# module_S-RX28_rev3_3_644.net
KiCad netlist of a schematic drawn in EAGLE
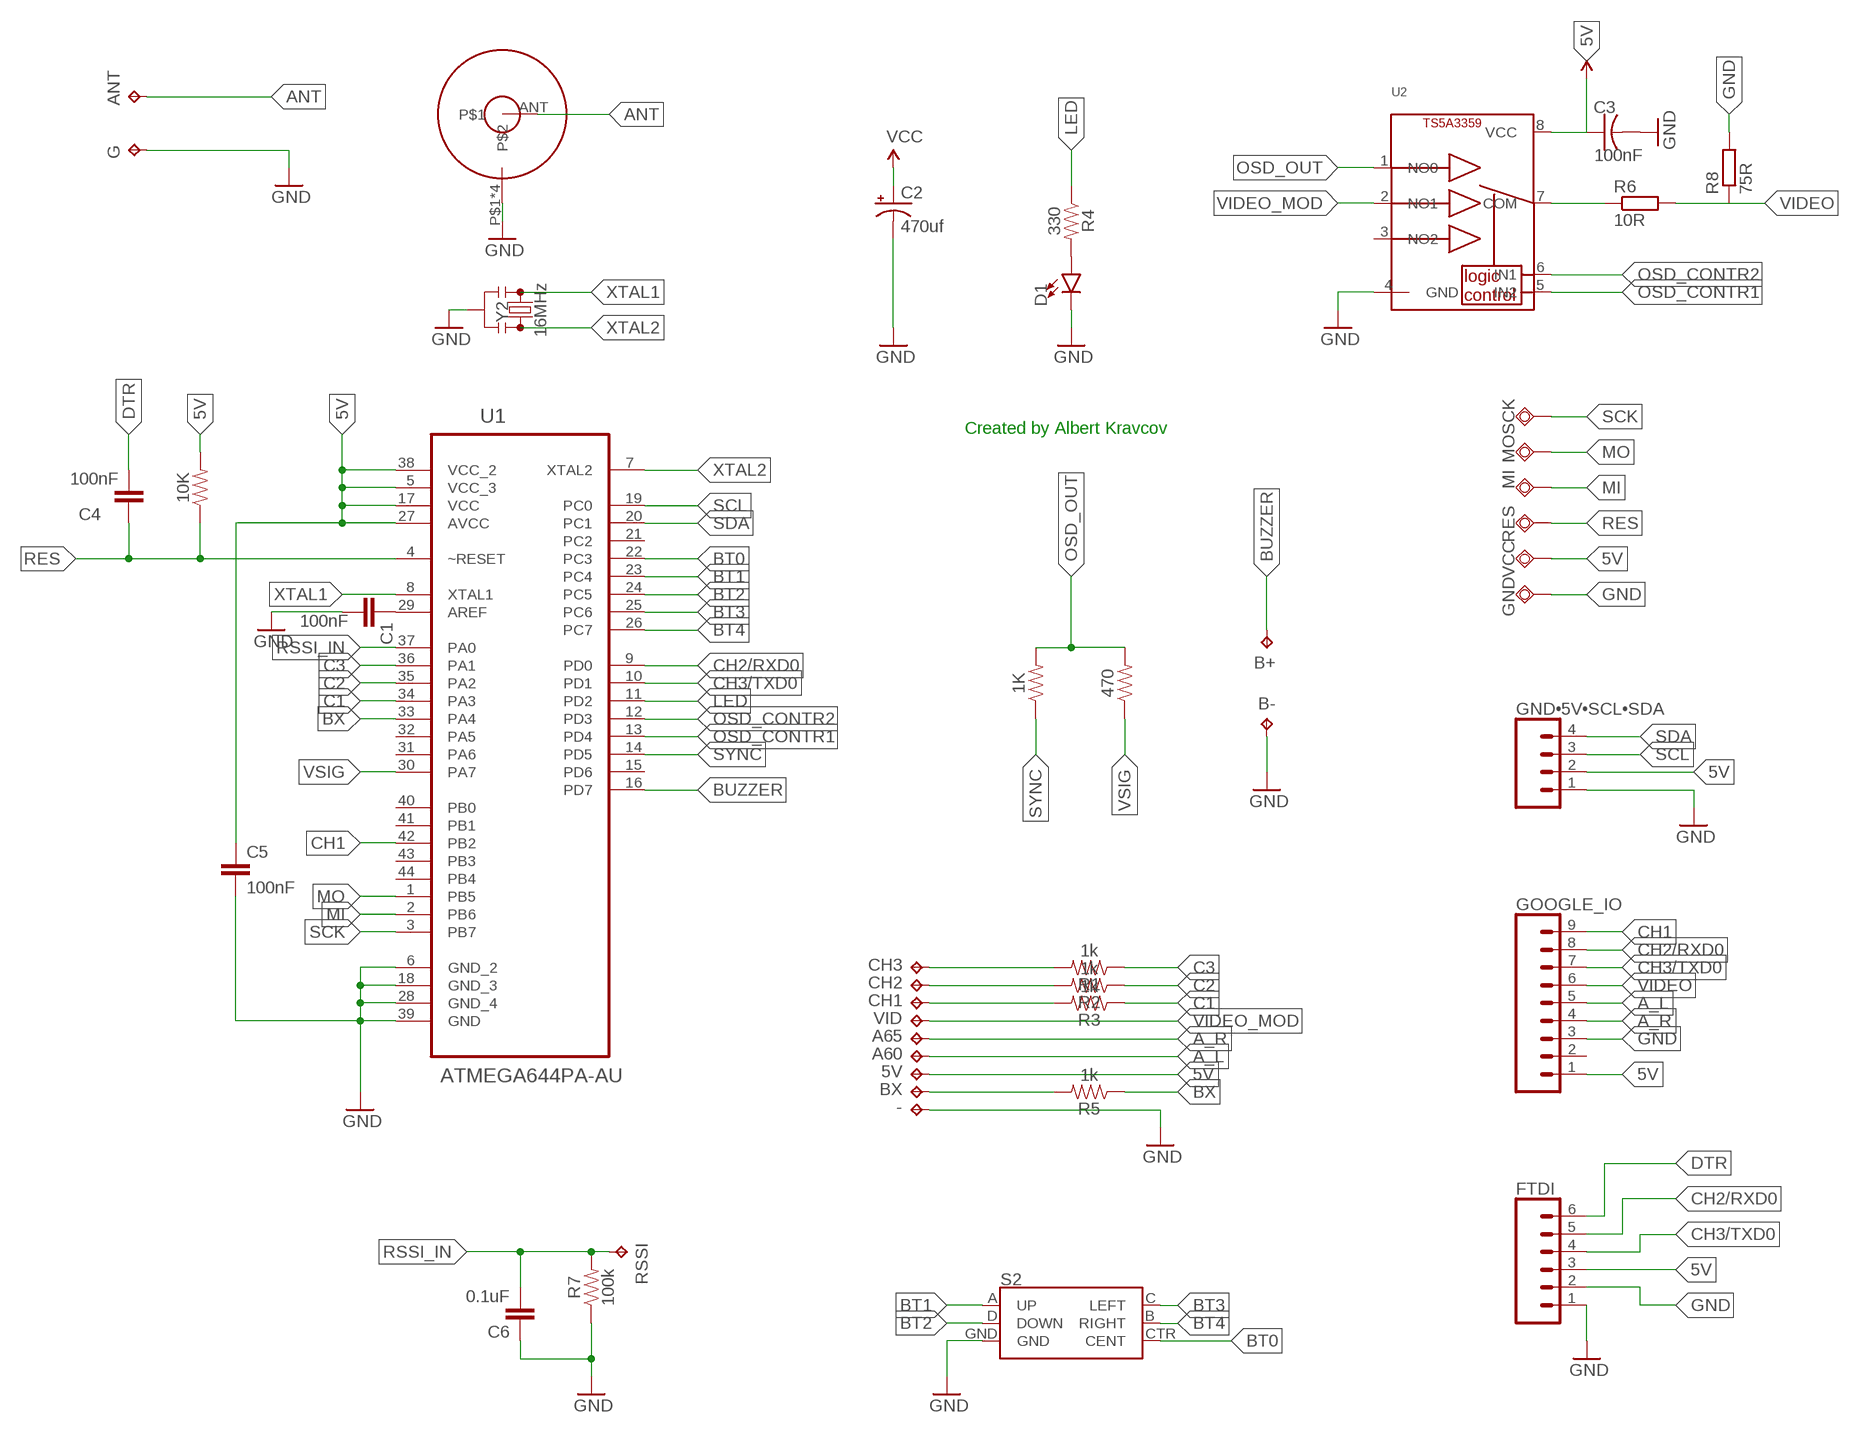
[diagram p0: schematic, sheet 1]

(export (version "E")
  (design (tool "Eeschema 10.0.6"))
  (components
    (comp (ref "-")
      (value "TPTP15SQ")
      (footprint "eagle-import:TP15SQ")
      (libsource (lib "eagle-import") (part "TPTP15SQ"))
    )
    (comp (ref "1K")
      (value "0.27OHM-0603-1/10W-1%")
      (footprint "eagle-import:0603")
      (libsource (lib "eagle-import") (part "0.27OHM-0603-1/10W-1%"))
    )
    (comp (ref "5V")
      (value "TPTP15SQ")
      (footprint "eagle-import:TP15SQ")
      (libsource (lib "eagle-import") (part "TPTP15SQ"))
    )
    (comp (ref "10K")
      (value "0.27OHM-0603-1/10W-1%")
      (footprint "eagle-import:0603")
      (libsource (lib "eagle-import") (part "0.27OHM-0603-1/10W-1%"))
    )
    (comp (ref "470")
      (value "0.27OHM-0603-1/10W-1%")
      (footprint "eagle-import:0603")
      (libsource (lib "eagle-import") (part "0.27OHM-0603-1/10W-1%"))
    )
    (comp (ref "A60")
      (value "TPTP15SQ")
      (footprint "eagle-import:TP15SQ")
      (libsource (lib "eagle-import") (part "TPTP15SQ"))
    )
    (comp (ref "A65")
      (value "TPTP15SQ")
      (footprint "eagle-import:TP15SQ")
      (libsource (lib "eagle-import") (part "TPTP15SQ"))
    )
    (comp (ref "ANT")
      (value "TPTP15R")
      (footprint "eagle-import:TP15R")
      (libsource (lib "eagle-import") (part "TPTP15R"))
    )
    (comp (ref "B+")
      (value "TPTP17SQ")
      (footprint "eagle-import:TP17SQ")
      (libsource (lib "eagle-import") (part "TPTP17SQ"))
    )
    (comp (ref "B-")
      (value "TPTP17SQ")
      (footprint "eagle-import:TP17SQ")
      (libsource (lib "eagle-import") (part "TPTP17SQ"))
    )
    (comp (ref "BX")
      (value "TPTP15SQ")
      (footprint "eagle-import:TP15SQ")
      (libsource (lib "eagle-import") (part "TPTP15SQ"))
    )
    (comp (ref "C1")
      (value "100nF")
      (footprint "eagle-import:0603")
      (libsource (lib "eagle-import") (part "10NF-0603-50V-10%"))
    )
    (comp (ref "C2")
      (value "470uf")
      (footprint "eagle-import:EIA7343")
      (libsource (lib "eagle-import") (part "CAP_POL7343"))
    )
    (comp (ref "C3")
      (value "100nF")
      (footprint "eagle-import:C0603")
      (libsource (lib "eagle-import") (part "C-USC0603"))
    )
    (comp (ref "C4")
      (value "100nF")
      (footprint "eagle-import:0603")
      (libsource (lib "eagle-import") (part "10NF-0603-50V-10%"))
    )
    (comp (ref "C5")
      (value "100nF")
      (footprint "eagle-import:0603")
      (libsource (lib "eagle-import") (part "10NF-0603-50V-10%"))
    )
    (comp (ref "C6")
      (value "0.1uF")
      (footprint "eagle-import:0603")
      (libsource (lib "eagle-import") (part "10NF-0603-50V-10%"))
    )
    (comp (ref "CH1")
      (value "TPTP15SQ")
      (footprint "eagle-import:TP15SQ")
      (libsource (lib "eagle-import") (part "TPTP15SQ"))
    )
    (comp (ref "CH2")
      (value "TPTP15SQ")
      (footprint "eagle-import:TP15SQ")
      (libsource (lib "eagle-import") (part "TPTP15SQ"))
    )
    (comp (ref "CH3")
      (value "TPTP15SQ")
      (footprint "eagle-import:TP15SQ")
      (libsource (lib "eagle-import") (part "TPTP15SQ"))
    )
    (comp (ref "D1")
      (value "LED0603")
      (footprint "eagle-import:LED-0603")
      (libsource (lib "eagle-import") (part "LED0603"))
    )
    (comp (ref "FTDI")
      (value "CONN_06SMD-1MM")
      (footprint "eagle-import:1X06-1MM")
      (libsource (lib "eagle-import") (part "CONN_06SMD-1MM"))
    )
    (comp (ref "G")
      (value "TPTP15SQ")
      (footprint "eagle-import:TP15SQ")
      (libsource (lib "eagle-import") (part "TPTP15SQ"))
    )
    (comp (ref "GND")
      (value "GND")
      (footprint "eagle-import:B1,27")
      (libsource (lib "eagle-import") (part "TPSQB1,27"))
    )
    (comp (ref "GND•5V•SCL•SDA")
      (value "CONN_04")
      (footprint "eagle-import:1X04")
      (libsource (lib "eagle-import") (part "CONN_04"))
    )
    (comp (ref "GOOGLE_IO")
      (value "CONN_09")
      (footprint "eagle-import:1X09")
      (libsource (lib "eagle-import") (part "CONN_09"))
    )
    (comp (ref "MI")
      (value "TPSQB1,27")
      (footprint "eagle-import:B1,27")
      (libsource (lib "eagle-import") (part "TPSQB1,27"))
    )
    (comp (ref "MO")
      (value "TPSQB1,27")
      (footprint "eagle-import:B1,27")
      (libsource (lib "eagle-import") (part "TPSQB1,27"))
    )
    (comp (ref "R1")
      (value "1k")
      (footprint "eagle-import:0603")
      (libsource (lib "eagle-import") (part "0.05OHM-0603-1/5W-1%"))
    )
    (comp (ref "R2")
      (value "1k")
      (footprint "eagle-import:0603")
      (libsource (lib "eagle-import") (part "0.05OHM-0603-1/5W-1%"))
    )
    (comp (ref "R3")
      (value "1k")
      (footprint "eagle-import:0603")
      (libsource (lib "eagle-import") (part "0.05OHM-0603-1/5W-1%"))
    )
    (comp (ref "R4")
      (value "330")
      (footprint "eagle-import:0603")
      (libsource (lib "eagle-import") (part "0.05OHM-0603-1/5W-1%"))
    )
    (comp (ref "R5")
      (value "1k")
      (footprint "eagle-import:0603")
      (libsource (lib "eagle-import") (part "0.05OHM-0603-1/5W-1%"))
    )
    (comp (ref "R6")
      (value "10R")
      (footprint "eagle-import:R0603")
      (libsource (lib "eagle-import") (part "R-EU_R0603"))
    )
    (comp (ref "R7")
      (value "100k")
      (footprint "eagle-import:0603")
      (libsource (lib "eagle-import") (part "0.05OHM-0603-1/5W-1%"))
    )
    (comp (ref "R8")
      (value "75R")
      (footprint "eagle-import:R0603")
      (libsource (lib "eagle-import") (part "R-EU_R0603"))
    )
    (comp (ref "RES")
      (value "TPSQB1,27")
      (footprint "eagle-import:B1,27")
      (libsource (lib "eagle-import") (part "TPSQB1,27"))
    )
    (comp (ref "RSSI")
      (value "TPTP15SQ")
      (footprint "eagle-import:TP15SQ")
      (libsource (lib "eagle-import") (part "TPTP15SQ"))
    )
    (comp (ref "S2")
      (value "JOYSTICK_MINI")
      (footprint "eagle-import:JOYSTICK_MINI")
      (libsource (lib "eagle-import") (part "JOYSTICK_MINI"))
    )
    (comp (ref "SCK")
      (value "TPSQB1,27")
      (footprint "eagle-import:B1,27")
      (libsource (lib "eagle-import") (part "TPSQB1,27"))
    )
    (comp (ref "U$1")
      (value "SMA_ANTENNA")
      (footprint "eagle-import:SMA_CONNECTOR")
      (libsource (lib "eagle-import") (part "SMA_ANTENNA"))
    )
    (comp (ref "U1")
      (value "ATMEGA644PA-AU")
      (footprint "eagle-import:QFP80P1200X1200X120-44N")
      (fields (field (name "MF") "Microchip"))
      (libsource (lib "eagle-import") (part "ATMEGA644PA-AU"))
    )
    (comp (ref "U2")
      (value "TS5A3359")
      (footprint "eagle-import:VFSOP-8")
      (libsource (lib "eagle-import") (part "TS5A3359"))
    )
    (comp (ref "VCC")
      (value "TPSQB1,27")
      (footprint "eagle-import:B1,27")
      (libsource (lib "eagle-import") (part "TPSQB1,27"))
    )
    (comp (ref "VID")
      (value "TPTP15SQ")
      (footprint "eagle-import:TP15SQ")
      (libsource (lib "eagle-import") (part "TPTP15SQ"))
    )
    (comp (ref "Y2")
      (value "16MHz")
      (footprint "eagle-import:RESONATOR-SMD-3.2X1.3")
      (libsource (lib "eagle-import") (part "RESONATOR-16MHZSMD_3.2X1.3"))
    )
  )
  (nets
    (net (code "1") (name "5V") (class "Default")
      (node (ref "10K") (pin "2") (pinfunction "2_2") (pintype "passive"))
      (node (ref "5V") (pin "TP") (pinfunction "TP_TP") (pintype "input"))
      (node (ref "C2") (pin "A") (pinfunction "+_A") (pintype "passive"))
      (node (ref "C3") (pin "1") (pinfunction "1_1") (pintype "passive"))
      (node (ref "C5") (pin "1") (pinfunction "1_1") (pintype "passive"))
      (node (ref "FTDI") (pin "3") (pinfunction "3_3") (pintype "passive"))
      (node (ref "GND•5V•SCL•SDA") (pin "2") (pinfunction "2_2") (pintype "passive"))
      (node (ref "GOOGLE_IO") (pin "1") (pinfunction "1_1") (pintype "passive"))
      (node (ref "U1") (pin "17") (pinfunction "VCC_17") (pintype "power_in"))
      (node (ref "U1") (pin "27") (pinfunction "AVCC_27") (pintype "power_in"))
      (node (ref "U1") (pin "38") (pinfunction "VCC_2_38") (pintype "power_in"))
      (node (ref "U1") (pin "5") (pinfunction "VCC_3_5") (pintype "power_in"))
      (node (ref "U2") (pin "8") (pinfunction "VCC_8") (pintype "power_in"))
      (node (ref "VCC") (pin "TP") (pinfunction "TP_TP") (pintype "input"))
    )
    (net (code "2") (name "ANT") (class "Default")
      (node (ref "ANT") (pin "TP") (pinfunction "TP_TP") (pintype "input"))
      (node (ref "U$1") (pin "ANT") (pinfunction "P$1_ANT") (pintype "bidirectional"))
    )
    (net (code "3") (name "A_L") (class "Default")
      (node (ref "A60") (pin "TP") (pinfunction "TP_TP") (pintype "input"))
      (node (ref "GOOGLE_IO") (pin "5") (pinfunction "5_5") (pintype "passive"))
    )
    (net (code "4") (name "A_R") (class "Default")
      (node (ref "A65") (pin "TP") (pinfunction "TP_TP") (pintype "input"))
      (node (ref "GOOGLE_IO") (pin "4") (pinfunction "4_4") (pintype "passive"))
    )
    (net (code "5") (name "BT0") (class "Default")
      (node (ref "S2") (pin "CTR") (pinfunction "CENT_CTR") (pintype "bidirectional"))
      (node (ref "U1") (pin "22") (pinfunction "PC3_22") (pintype "bidirectional"))
    )
    (net (code "6") (name "BT1") (class "Default")
      (node (ref "S2") (pin "A") (pinfunction "UP_A") (pintype "bidirectional"))
      (node (ref "U1") (pin "23") (pinfunction "PC4_23") (pintype "bidirectional"))
    )
    (net (code "7") (name "BT2") (class "Default")
      (node (ref "S2") (pin "D") (pinfunction "DOWN_D") (pintype "bidirectional"))
      (node (ref "U1") (pin "24") (pinfunction "PC5_24") (pintype "bidirectional"))
    )
    (net (code "8") (name "BT3") (class "Default")
      (node (ref "S2") (pin "C") (pinfunction "LEFT_C") (pintype "bidirectional"))
      (node (ref "U1") (pin "25") (pinfunction "PC6_25") (pintype "bidirectional"))
    )
    (net (code "9") (name "BT4") (class "Default")
      (node (ref "S2") (pin "B") (pinfunction "RIGHT_B") (pintype "bidirectional"))
      (node (ref "U1") (pin "26") (pinfunction "PC7_26") (pintype "bidirectional"))
    )
    (net (code "10") (name "BUZZER") (class "Default")
      (node (ref "B+") (pin "TP") (pinfunction "TP_TP") (pintype "input"))
      (node (ref "U1") (pin "16") (pinfunction "PD7_16") (pintype "bidirectional"))
    )
    (net (code "11") (name "BX") (class "Default")
      (node (ref "R5") (pin "1") (pinfunction "1_1") (pintype "passive"))
      (node (ref "U1") (pin "33") (pinfunction "PA4_33") (pintype "bidirectional"))
    )
    (net (code "12") (name "C1") (class "Default")
      (node (ref "R3") (pin "1") (pinfunction "1_1") (pintype "passive"))
      (node (ref "U1") (pin "34") (pinfunction "PA3_34") (pintype "bidirectional"))
    )
    (net (code "13") (name "C2") (class "Default")
      (node (ref "R2") (pin "1") (pinfunction "1_1") (pintype "passive"))
      (node (ref "U1") (pin "35") (pinfunction "PA2_35") (pintype "bidirectional"))
    )
    (net (code "14") (name "C3") (class "Default")
      (node (ref "R1") (pin "1") (pinfunction "1_1") (pintype "passive"))
      (node (ref "U1") (pin "36") (pinfunction "PA1_36") (pintype "bidirectional"))
    )
    (net (code "15") (name "CH1") (class "Default")
      (node (ref "GOOGLE_IO") (pin "9") (pinfunction "9_9") (pintype "passive"))
      (node (ref "U1") (pin "42") (pinfunction "PB2_42") (pintype "bidirectional"))
    )
    (net (code "16") (name "CH2{slash}RXD0") (class "Default")
      (node (ref "FTDI") (pin "5") (pinfunction "5_5") (pintype "passive"))
      (node (ref "GOOGLE_IO") (pin "8") (pinfunction "8_8") (pintype "passive"))
      (node (ref "U1") (pin "9") (pinfunction "PD0_9") (pintype "bidirectional"))
    )
    (net (code "17") (name "CH3{slash}TXD0") (class "Default")
      (node (ref "FTDI") (pin "4") (pinfunction "4_4") (pintype "passive"))
      (node (ref "GOOGLE_IO") (pin "7") (pinfunction "7_7") (pintype "passive"))
      (node (ref "U1") (pin "10") (pinfunction "PD1_10") (pintype "bidirectional"))
    )
    (net (code "18") (name "DTR") (class "Default")
      (node (ref "C4") (pin "2") (pinfunction "2_2") (pintype "passive"))
      (node (ref "FTDI") (pin "6") (pinfunction "6_6") (pintype "passive"))
    )
    (net (code "19") (name "GND") (class "Default")
      (node (ref "-") (pin "TP") (pinfunction "TP_TP") (pintype "input"))
      (node (ref "B-") (pin "TP") (pinfunction "TP_TP") (pintype "input"))
      (node (ref "C1") (pin "2") (pinfunction "2_2") (pintype "passive"))
      (node (ref "C2") (pin "C") (pinfunction "-_C") (pintype "passive"))
      (node (ref "C3") (pin "2") (pinfunction "2_2") (pintype "passive"))
      (node (ref "C5") (pin "2") (pinfunction "2_2") (pintype "passive"))
      (node (ref "C6") (pin "1") (pinfunction "1_1") (pintype "passive"))
      (node (ref "D1") (pin "C") (pinfunction "C_C") (pintype "passive"))
      (node (ref "FTDI") (pin "1") (pinfunction "1_1") (pintype "passive"))
      (node (ref "FTDI") (pin "2") (pinfunction "2_2") (pintype "passive"))
      (node (ref "G") (pin "TP") (pinfunction "TP_TP") (pintype "input"))
      (node (ref "GND") (pin "TP") (pinfunction "TP_TP") (pintype "input"))
      (node (ref "GND•5V•SCL•SDA") (pin "1") (pinfunction "1_1") (pintype "passive"))
      (node (ref "GOOGLE_IO") (pin "3") (pinfunction "3_3") (pintype "passive"))
      (node (ref "R7") (pin "1") (pinfunction "1_1") (pintype "passive"))
      (node (ref "R8") (pin "2") (pinfunction "2_2") (pintype "passive"))
      (node (ref "S2") (pin "GND") (pinfunction "GND_GND") (pintype "bidirectional"))
      (node (ref "U$1") (pin "P$1") (pinfunction "P$2_P$1") (pintype "bidirectional"))
      (node (ref "U$1") (pin "P$2") (pinfunction "P$2_P$2") (pintype "bidirectional"))
      (node (ref "U$1") (pin "P$3") (pinfunction "P$2_P$3") (pintype "bidirectional"))
      (node (ref "U$1") (pin "P$4") (pinfunction "P$2_P$4") (pintype "bidirectional"))
      (node (ref "U1") (pin "18") (pinfunction "GND_3_18") (pintype "passive"))
      (node (ref "U1") (pin "28") (pinfunction "GND_4_28") (pintype "passive"))
      (node (ref "U1") (pin "39") (pinfunction "GND_39") (pintype "passive"))
      (node (ref "U1") (pin "6") (pinfunction "GND_2_6") (pintype "passive"))
      (node (ref "U2") (pin "4") (pinfunction "GND_4") (pintype "power_in"))
      (node (ref "Y2") (pin "2") (pinfunction "2_2") (pintype "passive"))
    )
    (net (code "20") (name "LED") (class "Default")
      (node (ref "R4") (pin "1") (pinfunction "1_1") (pintype "passive"))
      (node (ref "U1") (pin "11") (pinfunction "PD2_11") (pintype "bidirectional"))
    )
    (net (code "21") (name "MI") (class "Default")
      (node (ref "MI") (pin "TP") (pinfunction "TP_TP") (pintype "input"))
      (node (ref "U1") (pin "2") (pinfunction "PB6_2") (pintype "bidirectional"))
    )
    (net (code "22") (name "MO") (class "Default")
      (node (ref "MO") (pin "TP") (pinfunction "TP_TP") (pintype "input"))
      (node (ref "U1") (pin "1") (pinfunction "PB5_1") (pintype "bidirectional"))
    )
    (net (code "23") (name "Net-(BX-PadTP)") (class "Default")
      (node (ref "BX") (pin "TP") (pinfunction "TP_TP") (pintype "input"))
      (node (ref "R5") (pin "2") (pinfunction "2_2") (pintype "passive"))
    )
    (net (code "24") (name "Net-(CH1-PadTP)") (class "Default")
      (node (ref "CH1") (pin "TP") (pinfunction "TP_TP") (pintype "input"))
      (node (ref "R3") (pin "2") (pinfunction "2_2") (pintype "passive"))
    )
    (net (code "25") (name "Net-(CH2-PadTP)") (class "Default")
      (node (ref "CH2") (pin "TP") (pinfunction "TP_TP") (pintype "input"))
      (node (ref "R2") (pin "2") (pinfunction "2_2") (pintype "passive"))
    )
    (net (code "26") (name "Net-(CH3-PadTP)") (class "Default")
      (node (ref "CH3") (pin "TP") (pinfunction "TP_TP") (pintype "input"))
      (node (ref "R1") (pin "2") (pinfunction "2_2") (pintype "passive"))
    )
    (net (code "27") (name "Net-(D1-PadA)") (class "Default")
      (node (ref "D1") (pin "A") (pinfunction "A_A") (pintype "passive"))
      (node (ref "R4") (pin "2") (pinfunction "2_2") (pintype "passive"))
    )
    (net (code "28") (name "Net-(U1-AREF)") (class "Default")
      (node (ref "C1") (pin "1") (pinfunction "1_1") (pintype "passive"))
      (node (ref "U1") (pin "29") (pinfunction "AREF_29") (pintype "input"))
    )
    (net (code "29") (name "Net-(U2-COM)") (class "Default")
      (node (ref "R6") (pin "1") (pinfunction "1_1") (pintype "passive"))
      (node (ref "U2") (pin "7") (pinfunction "COM_7") (pintype "input"))
    )
    (net (code "30") (name "OSD_CONTR1") (class "Default")
      (node (ref "U1") (pin "13") (pinfunction "PD4_13") (pintype "bidirectional"))
      (node (ref "U2") (pin "5") (pinfunction "IN2_5") (pintype "output"))
    )
    (net (code "31") (name "OSD_CONTR2") (class "Default")
      (node (ref "U1") (pin "12") (pinfunction "PD3_12") (pintype "bidirectional"))
      (node (ref "U2") (pin "6") (pinfunction "IN1_6") (pintype "output"))
    )
    (net (code "32") (name "OSD_OUT") (class "Default")
      (node (ref "1K") (pin "2") (pinfunction "2_2") (pintype "passive"))
      (node (ref "470") (pin "2") (pinfunction "2_2") (pintype "passive"))
      (node (ref "U2") (pin "1") (pinfunction "NO0_1") (pintype "input"))
    )
    (net (code "33") (name "RES") (class "Default")
      (node (ref "10K") (pin "1") (pinfunction "1_1") (pintype "passive"))
      (node (ref "C4") (pin "1") (pinfunction "1_1") (pintype "passive"))
      (node (ref "RES") (pin "TP") (pinfunction "TP_TP") (pintype "input"))
      (node (ref "U1") (pin "4") (pinfunction "~{RESET}_4") (pintype "input"))
    )
    (net (code "34") (name "RSSI_IN") (class "Default")
      (node (ref "C6") (pin "2") (pinfunction "2_2") (pintype "passive"))
      (node (ref "R7") (pin "2") (pinfunction "2_2") (pintype "passive"))
      (node (ref "RSSI") (pin "TP") (pinfunction "TP_TP") (pintype "input"))
      (node (ref "U1") (pin "37") (pinfunction "PA0_37") (pintype "bidirectional"))
    )
    (net (code "35") (name "SCK") (class "Default")
      (node (ref "SCK") (pin "TP") (pinfunction "TP_TP") (pintype "input"))
      (node (ref "U1") (pin "3") (pinfunction "PB7_3") (pintype "bidirectional"))
    )
    (net (code "36") (name "SCL") (class "Default")
      (node (ref "GND•5V•SCL•SDA") (pin "3") (pinfunction "3_3") (pintype "passive"))
      (node (ref "U1") (pin "19") (pinfunction "PC0_19") (pintype "bidirectional"))
    )
    (net (code "37") (name "SDA") (class "Default")
      (node (ref "GND•5V•SCL•SDA") (pin "4") (pinfunction "4_4") (pintype "passive"))
      (node (ref "U1") (pin "20") (pinfunction "PC1_20") (pintype "bidirectional"))
    )
    (net (code "38") (name "SYNC") (class "Default")
      (node (ref "1K") (pin "1") (pinfunction "1_1") (pintype "passive"))
      (node (ref "U1") (pin "14") (pinfunction "PD5_14") (pintype "bidirectional"))
    )
    (net (code "39") (name "VIDEO") (class "Default")
      (node (ref "GOOGLE_IO") (pin "6") (pinfunction "6_6") (pintype "passive"))
      (node (ref "R6") (pin "2") (pinfunction "2_2") (pintype "passive"))
      (node (ref "R8") (pin "1") (pinfunction "1_1") (pintype "passive"))
    )
    (net (code "40") (name "VIDEO_MOD") (class "Default")
      (node (ref "U2") (pin "2") (pinfunction "NO1_2") (pintype "input"))
      (node (ref "VID") (pin "TP") (pinfunction "TP_TP") (pintype "input"))
    )
    (net (code "41") (name "VSIG") (class "Default")
      (node (ref "470") (pin "1") (pinfunction "1_1") (pintype "passive"))
      (node (ref "U1") (pin "30") (pinfunction "PA7_30") (pintype "bidirectional"))
    )
    (net (code "42") (name "XTAL1") (class "Default")
      (node (ref "U1") (pin "8") (pinfunction "XTAL1_8") (pintype "input"))
      (node (ref "Y2") (pin "1") (pinfunction "1_1") (pintype "passive"))
    )
    (net (code "43") (name "XTAL2") (class "Default")
      (node (ref "U1") (pin "7") (pinfunction "XTAL2_7") (pintype "output"))
      (node (ref "Y2") (pin "3") (pinfunction "3_3") (pintype "passive"))
    )
    (net (code "44") (name "unconnected-(GOOGLE_IO-Pad2)") (class "Default")
      (node (ref "GOOGLE_IO") (pin "2") (pinfunction "2_2") (pintype "passive"))
    )
    (net (code "45") (name "unconnected-(U1-PA5-Pad32)") (class "Default")
      (node (ref "U1") (pin "32") (pinfunction "PA5_32") (pintype "bidirectional"))
    )
    (net (code "46") (name "unconnected-(U1-PA6-Pad31)") (class "Default")
      (node (ref "U1") (pin "31") (pinfunction "PA6_31") (pintype "bidirectional"))
    )
    (net (code "47") (name "unconnected-(U1-PB0-Pad40)") (class "Default")
      (node (ref "U1") (pin "40") (pinfunction "PB0_40") (pintype "bidirectional"))
    )
    (net (code "48") (name "unconnected-(U1-PB1-Pad41)") (class "Default")
      (node (ref "U1") (pin "41") (pinfunction "PB1_41") (pintype "bidirectional"))
    )
    (net (code "49") (name "unconnected-(U1-PB3-Pad43)") (class "Default")
      (node (ref "U1") (pin "43") (pinfunction "PB3_43") (pintype "bidirectional"))
    )
    (net (code "50") (name "unconnected-(U1-PB4-Pad44)") (class "Default")
      (node (ref "U1") (pin "44") (pinfunction "PB4_44") (pintype "bidirectional"))
    )
    (net (code "51") (name "unconnected-(U1-PC2-Pad21)") (class "Default")
      (node (ref "U1") (pin "21") (pinfunction "PC2_21") (pintype "bidirectional"))
    )
    (net (code "52") (name "unconnected-(U1-PD6-Pad15)") (class "Default")
      (node (ref "U1") (pin "15") (pinfunction "PD6_15") (pintype "bidirectional"))
    )
    (net (code "53") (name "unconnected-(U2-NO2-Pad3)") (class "Default")
      (node (ref "U2") (pin "3") (pinfunction "NO2_3") (pintype "input"))
    )
  )
)
